# dcdc.net
KiCad netlist of a schematic drawn in EAGLE
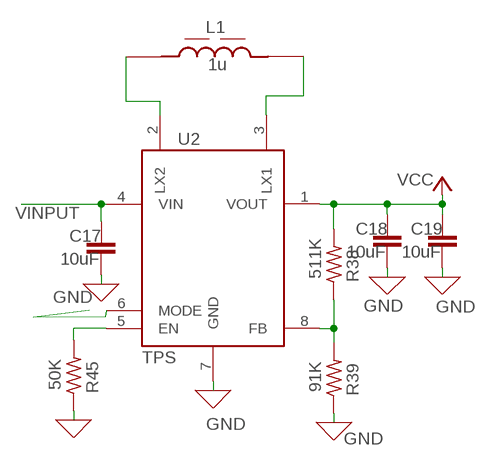
[diagram p0: schematic, sheet 1]

(export (version "E")
  (design (tool "Eeschema 10.0.6"))
  (components
    (comp (ref "C17")
      (value "10uF")
      (footprint "eagle-import:C0805")
      (libsource (lib "eagle-import") (part "C-EUC0805"))
    )
    (comp (ref "C18")
      (value "10uF")
      (footprint "eagle-import:C0805")
      (libsource (lib "eagle-import") (part "C-EUC0805"))
    )
    (comp (ref "C19")
      (value "10uF")
      (footprint "eagle-import:C0805")
      (libsource (lib "eagle-import") (part "C-EUC0805"))
    )
    (comp (ref "L1")
      (value "1u")
      (footprint "eagle-import:IND_74404043220A")
      (fields (field (name "MF") "Wurth Electronics") (field (name "MP") "74404043220A"))
      (libsource (lib "eagle-import") (part "5040_INDUCTOR"))
    )
    (comp (ref "R38")
      (value "511K")
      (footprint "eagle-import:M0805")
      (libsource (lib "eagle-import") (part "R-US_M0805"))
    )
    (comp (ref "R39")
      (value "91K")
      (footprint "eagle-import:M0805")
      (libsource (lib "eagle-import") (part "R-US_M0805"))
    )
    (comp (ref "R45")
      (value "50K")
      (footprint "eagle-import:M0805")
      (libsource (lib "eagle-import") (part "R-US_M0805"))
    )
    (comp (ref "U2")
      (value "TPS")
      (footprint "eagle-import:SOTFL50P160X60-8N")
      (fields (field (name "MF") "Texas Instruments") (field (name "MP") "TPS563212DRLR"))
      (libsource (lib "eagle-import") (part "TPS563212DRLR"))
    )
  )
  (nets
    (net (code "1") (name "/VINPUT") (class "Default")
      (node (ref "C17") (pin "1") (pinfunction "1_1") (pintype "passive"))
      (node (ref "U2") (pin "4") (pinfunction "VIN_4") (pintype "input"))
    )
    (net (code "2") (name "GND") (class "Default")
      (node (ref "C17") (pin "2") (pinfunction "2_2") (pintype "passive"))
      (node (ref "C18") (pin "2") (pinfunction "2_2") (pintype "passive"))
      (node (ref "C19") (pin "2") (pinfunction "2_2") (pintype "passive"))
      (node (ref "R39") (pin "1") (pinfunction "1_1") (pintype "passive"))
      (node (ref "R45") (pin "1") (pinfunction "1_1") (pintype "passive"))
      (node (ref "U2") (pin "7") (pinfunction "GND_7") (pintype "power_in"))
    )
    (net (code "3") (name "Net-(U2-EN)") (class "Default")
      (node (ref "R45") (pin "2") (pinfunction "2_2") (pintype "passive"))
      (node (ref "U2") (pin "5") (pinfunction "EN_5") (pintype "bidirectional"))
    )
    (net (code "4") (name "Net-(U2-FB)") (class "Default")
      (node (ref "R38") (pin "1") (pinfunction "1_1") (pintype "passive"))
      (node (ref "R39") (pin "2") (pinfunction "2_2") (pintype "passive"))
      (node (ref "U2") (pin "8") (pinfunction "FB_8") (pintype "input"))
    )
    (net (code "5") (name "Net-(U2-LX1)") (class "Default")
      (node (ref "L1") (pin "2") (pinfunction "2_2") (pintype "passive"))
      (node (ref "U2") (pin "3") (pinfunction "LX1_3") (pintype "output"))
    )
    (net (code "6") (name "Net-(U2-LX2)") (class "Default")
      (node (ref "L1") (pin "1") (pinfunction "1_1") (pintype "passive"))
      (node (ref "U2") (pin "2") (pinfunction "LX2_2") (pintype "input"))
    )
    (net (code "7") (name "VCC") (class "Default")
      (node (ref "C18") (pin "1") (pinfunction "1_1") (pintype "passive"))
      (node (ref "C19") (pin "1") (pinfunction "1_1") (pintype "passive"))
      (node (ref "R38") (pin "2") (pinfunction "2_2") (pintype "passive"))
      (node (ref "U2") (pin "1") (pinfunction "VOUT_1") (pintype "bidirectional"))
    )
    (net (code "8") (name "unconnected-(U2-MODE-Pad6)") (class "Default")
      (node (ref "U2") (pin "6") (pinfunction "MODE_6") (pintype "bidirectional"))
    )
  )
)
